# CAN_UART.net
KiCad netlist of a schematic drawn in Altium Designer
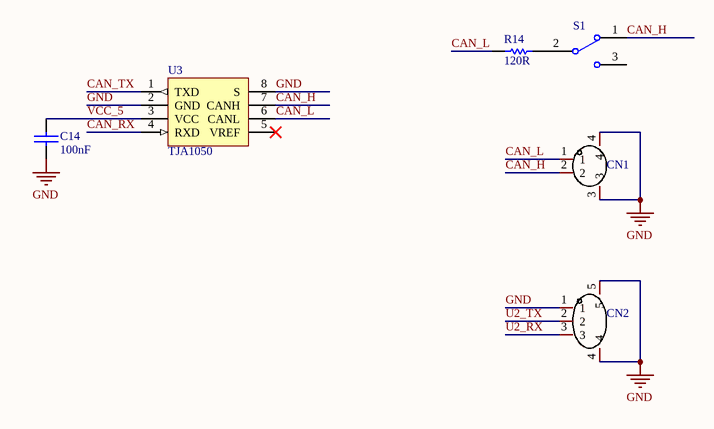
[diagram p0: CAN_UART.SchDoc]

(export (version "E")
  (design (tool "Eeschema 10.0.6"))
  (components
    (comp (ref "C14")
      (value "100nF")
      (footprint "C 0603_L")
      (description "无极性电容")
      (libsource (lib "电容") (part "CAP"))
    )
    (comp (ref "CN1")
      (value "GH-1.25-2P")
      (footprint "GH1.25-WT-2P")
      (libsource (lib "GH-1.25") (part "GH-1.25-2P"))
    )
    (comp (ref "CN2")
      (value "GH-1.25-3P")
      (footprint "GH1.25-WT-3P")
      (libsource (lib "GH-1.25") (part "GH-1.25-3P"))
    )
    (comp (ref "R14") (value "120R") (footprint "0603R") (libsource (lib "电阻") (part "RES")))
    (comp (ref "S1")
      (value "SS-12F23")
      (footprint "SK12D07VG3")
      (description "1路波动开关")
      (fields (field (name "版权归属") "封装库来自淘宝 ID：黄晶宝石"))
      (libsource (lib "0.7 - 常用按键-开关") (part "SSW-1P"))
    )
    (comp (ref "U3")
      (value "TJA1050")
      (footprint "SOP8_N")
      (description "CAN总线收发芯片")
      (fields (field (name "版权归属") "封装库来自淘宝 ID：黄晶宝石"))
      (libsource (lib "1.0 - 常见芯片") (part "TJA1050"))
    )
  )
  (nets
    (net (code "1") (name "/CAN_H") (class "Default")
      (node (ref "CN1") (pin "2") (pinfunction "2_2") (pintype "passive"))
      (node (ref "S1") (pin "1") (pinfunction "1_1") (pintype "passive"))
      (node (ref "U3") (pin "7") (pinfunction "CANH_7") (pintype "passive"))
    )
    (net (code "2") (name "/CAN_L") (class "Default")
      (node (ref "CN1") (pin "1") (pinfunction "1_1") (pintype "passive"))
      (node (ref "R14") (pin "2") (pinfunction "2_2") (pintype "passive"))
      (node (ref "U3") (pin "6") (pinfunction "CANL_6") (pintype "passive"))
    )
    (net (code "3") (name "/CAN_RX") (class "Default")
      (node (ref "U3") (pin "4") (pinfunction "RXD_4") (pintype "input"))
    )
    (net (code "4") (name "/CAN_TX") (class "Default")
      (node (ref "U3") (pin "1") (pinfunction "TXD_1") (pintype "output"))
    )
    (net (code "5") (name "/U2_RX") (class "Default")
      (node (ref "CN2") (pin "3") (pinfunction "3_3") (pintype "passive"))
    )
    (net (code "6") (name "/U2_TX") (class "Default")
      (node (ref "CN2") (pin "2") (pinfunction "2_2") (pintype "passive"))
    )
    (net (code "7") (name "/VCC_5") (class "Default")
      (node (ref "C14") (pin "2") (pinfunction "2_2") (pintype "passive"))
      (node (ref "U3") (pin "3") (pinfunction "VCC_3") (pintype "passive"))
    )
    (net (code "8") (name "GND") (class "Default")
      (node (ref "C14") (pin "1") (pinfunction "1_1") (pintype "passive"))
      (node (ref "CN1") (pin "3") (pinfunction "3_3") (pintype "passive"))
      (node (ref "CN1") (pin "4") (pinfunction "4_4") (pintype "passive"))
      (node (ref "CN2") (pin "1") (pinfunction "1_1") (pintype "passive"))
      (node (ref "CN2") (pin "4") (pinfunction "4_4") (pintype "passive"))
      (node (ref "CN2") (pin "5") (pinfunction "5_5") (pintype "passive"))
      (node (ref "U3") (pin "2") (pinfunction "GND_2") (pintype "passive"))
      (node (ref "U3") (pin "8") (pinfunction "S_8") (pintype "passive"))
    )
    (net (code "9") (name "Net-(R14-Pad1)") (class "Default")
      (node (ref "R14") (pin "1") (pinfunction "1_1") (pintype "passive"))
      (node (ref "S1") (pin "2") (pinfunction "2_2") (pintype "passive"))
    )
    (net (code "10") (name "unconnected-(S1-Pad3)") (class "Default")
      (node (ref "S1") (pin "3") (pinfunction "3_3") (pintype "passive"))
    )
    (net (code "11") (name "unconnected-(U3-VREF-Pad5)") (class "Default")
      (node (ref "U3") (pin "5") (pinfunction "VREF_5") (pintype "passive+no_connect"))
    )
  )
)
